# Isolation-Buffers.net
KiCad netlist of a schematic drawn in Altium Designer
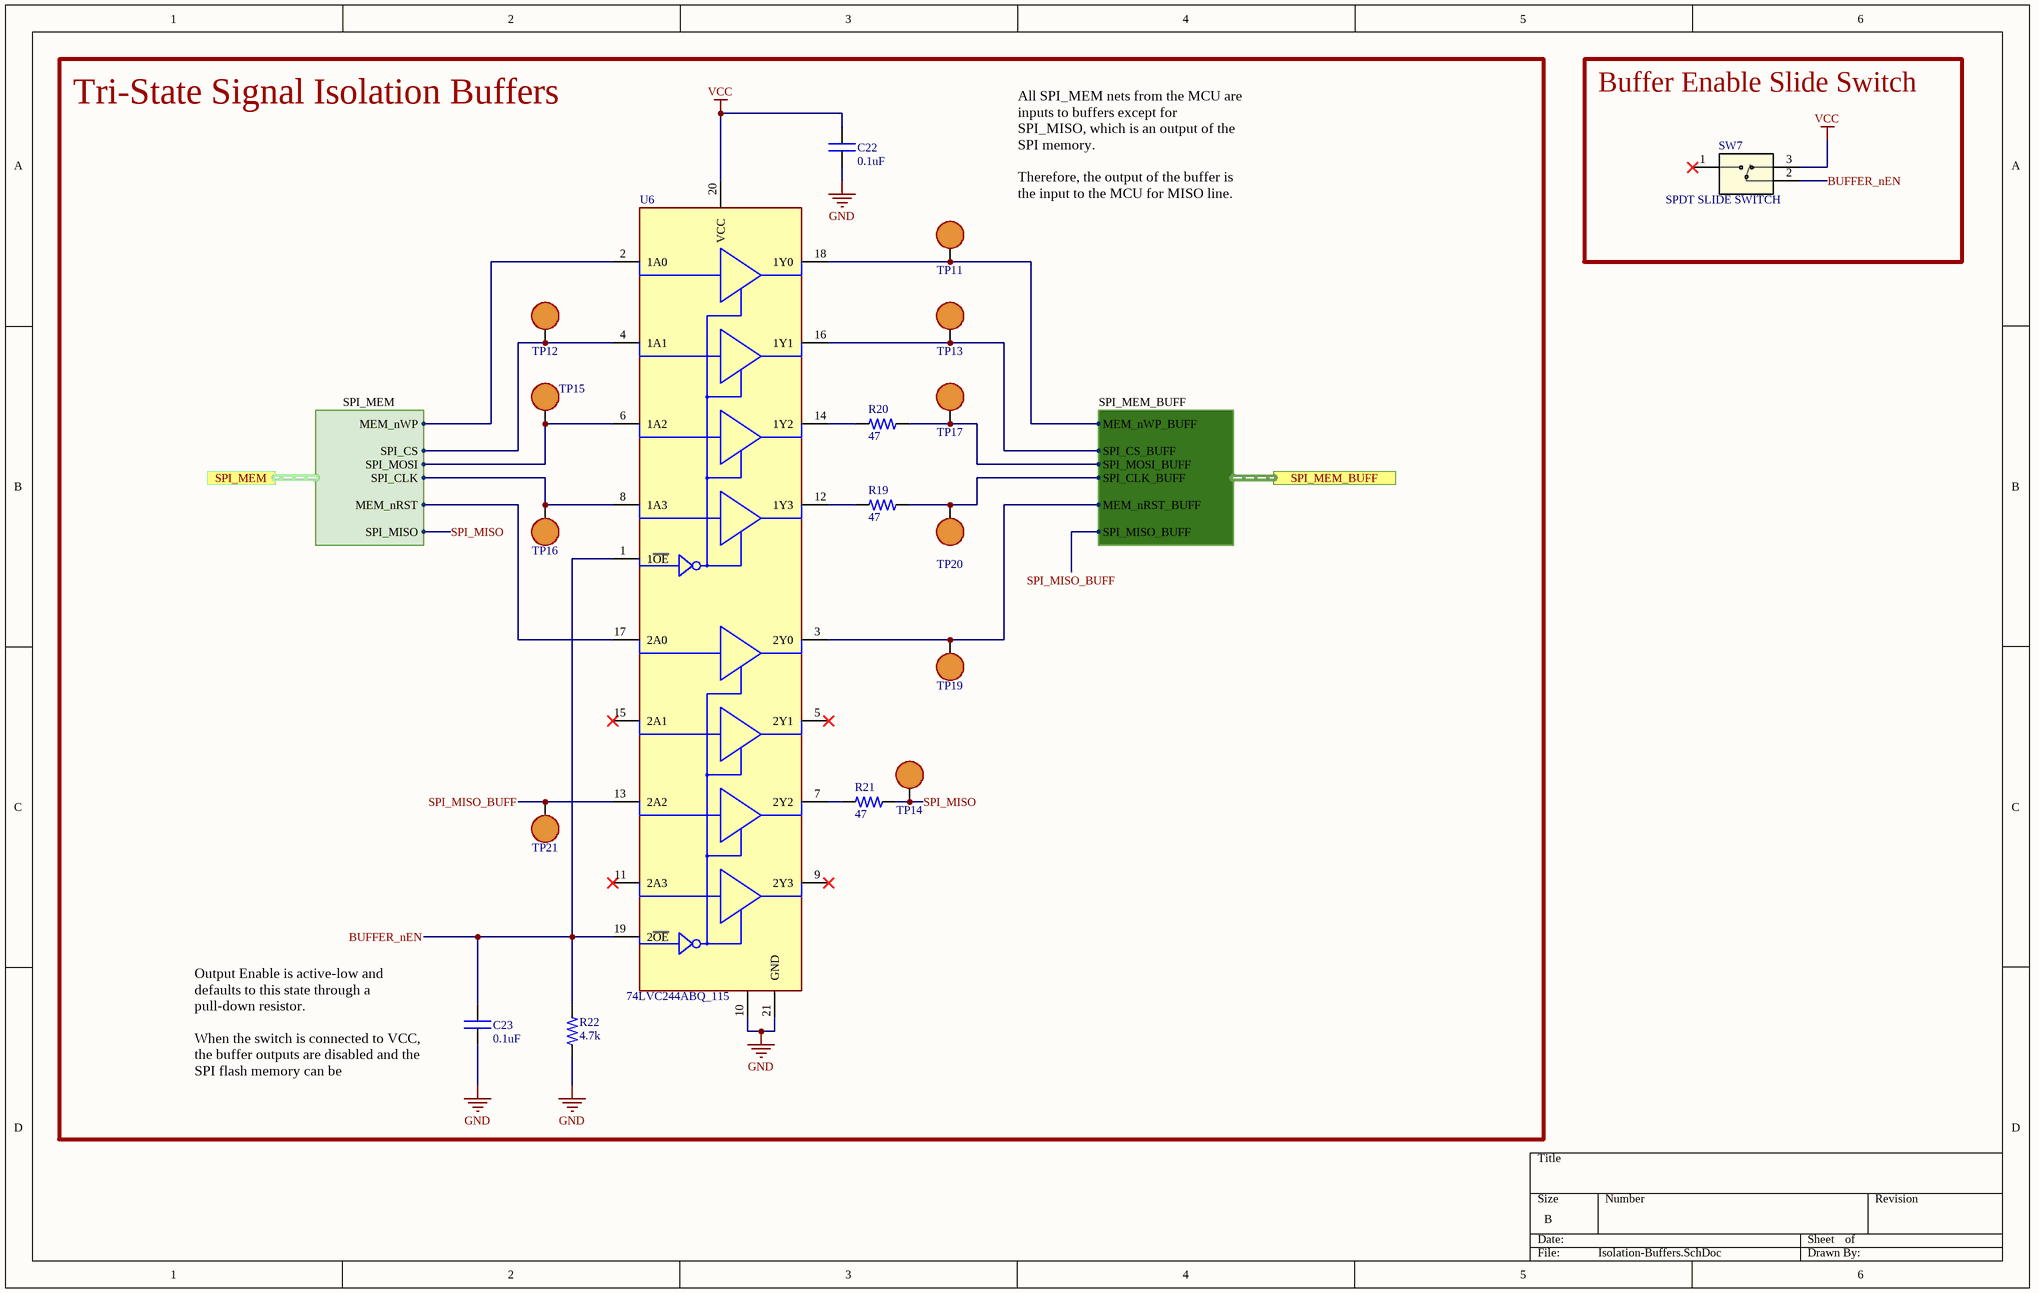
[diagram p0: Isolation-Buffers.SchDoc]

(export (version "E")
  (design (tool "Eeschema 10.0.6"))
  (components
    (comp (ref "C22")
      (value "0.1uF")
      (footprint "Beethoven-clock:0402C")
      (description "Capacitor")
      (fields (field (name "MFR") "Murata Electronics") (field (name "Comment") "CAP"))
      (libsource (lib "Beethoven-clock") (part "CAP"))
    )
    (comp (ref "C23")
      (value "0.1uF")
      (footprint "Beethoven-clock:0402C")
      (description "Capacitor")
      (fields (field (name "MFR") "Murata Electronics") (field (name "Comment") "CAP"))
      (libsource (lib "Beethoven-clock") (part "CAP"))
    )
    (comp (ref "R19")
      (value "47")
      (footprint "Beethoven-clock:0402R")
      (description "Resistor")
      (fields (field (name "MFR") "YAGEO") (field (name "Comment") "RES"))
      (libsource (lib "Beethoven-clock") (part "RES"))
    )
    (comp (ref "R20")
      (value "47")
      (footprint "Beethoven-clock:0402R")
      (description "Resistor")
      (fields (field (name "MFR") "YAGEO") (field (name "Comment") "RES"))
      (libsource (lib "Beethoven-clock") (part "RES"))
    )
    (comp (ref "R21")
      (value "47")
      (footprint "Beethoven-clock:0402R")
      (description "Resistor")
      (fields (field (name "MFR") "YAGEO") (field (name "Comment") "RES"))
      (libsource (lib "Beethoven-clock") (part "RES"))
    )
    (comp (ref "R22")
      (value "4.7k")
      (footprint "Beethoven-clock:0402R")
      (description "Resistor")
      (fields (field (name "MFR") "YAGEO") (field (name "Comment") "RES"))
      (libsource (lib "Beethoven-clock") (part "RES"))
    )
    (comp (ref "SW7")
      (value "SPDT SLIDE SWITCH")
      (footprint "Beethoven-clock:JS102011SCQN")
      (fields (field (name "MFR") "C&K"))
      (libsource (lib "Beethoven-clock") (part "SPDT SLIDE SWITCH"))
    )
    (comp (ref "TP11")
      (value "RCWCTE")
      (footprint "Beethoven-clock:RCWCTE")
      (description "Test Point, Surface Mount")
      (fields (field (name "MFR") "KOA Speer Electronics, Inc."))
      (libsource (lib "Beethoven-clock") (part "TEST POINT"))
    )
    (comp (ref "TP12")
      (value "RCWCTE")
      (footprint "Beethoven-clock:RCWCTE")
      (description "Test Point, Surface Mount")
      (fields (field (name "MFR") "KOA Speer Electronics, Inc."))
      (libsource (lib "Beethoven-clock") (part "TEST POINT"))
    )
    (comp (ref "TP13")
      (value "RCWCTE")
      (footprint "Beethoven-clock:RCWCTE")
      (description "Test Point, Surface Mount")
      (fields (field (name "MFR") "KOA Speer Electronics, Inc."))
      (libsource (lib "Beethoven-clock") (part "TEST POINT"))
    )
    (comp (ref "TP14")
      (value "RCWCTE")
      (footprint "Beethoven-clock:RCWCTE")
      (description "Test Point, Surface Mount")
      (fields (field (name "MFR") "KOA Speer Electronics, Inc."))
      (libsource (lib "Beethoven-clock") (part "TEST POINT"))
    )
    (comp (ref "TP15")
      (value "RCWCTE")
      (footprint "Beethoven-clock:RCWCTE")
      (description "Test Point, Surface Mount")
      (fields (field (name "MFR") "KOA Speer Electronics, Inc."))
      (libsource (lib "Beethoven-clock") (part "TEST POINT"))
    )
    (comp (ref "TP16")
      (value "RCWCTE")
      (footprint "Beethoven-clock:RCWCTE")
      (description "Test Point, Surface Mount")
      (fields (field (name "MFR") "KOA Speer Electronics, Inc."))
      (libsource (lib "Beethoven-clock") (part "TEST POINT"))
    )
    (comp (ref "TP17")
      (value "RCWCTE")
      (footprint "Beethoven-clock:RCWCTE")
      (description "Test Point, Surface Mount")
      (fields (field (name "MFR") "KOA Speer Electronics, Inc."))
      (libsource (lib "Beethoven-clock") (part "TEST POINT"))
    )
    (comp (ref "TP19")
      (value "RCWCTE")
      (footprint "Beethoven-clock:RCWCTE")
      (description "Test Point, Surface Mount")
      (fields (field (name "MFR") "KOA Speer Electronics, Inc."))
      (libsource (lib "Beethoven-clock") (part "TEST POINT"))
    )
    (comp (ref "TP20")
      (value "RCWCTE")
      (footprint "Beethoven-clock:RCWCTE")
      (description "Test Point, Surface Mount")
      (fields (field (name "MFR") "KOA Speer Electronics, Inc."))
      (libsource (lib "Beethoven-clock") (part "TEST POINT"))
    )
    (comp (ref "TP21")
      (value "RCWCTE")
      (footprint "Beethoven-clock:RCWCTE")
      (description "Test Point, Surface Mount")
      (fields (field (name "MFR") "KOA Speer Electronics, Inc."))
      (libsource (lib "Beethoven-clock") (part "TEST POINT"))
    )
    (comp (ref "U6")
      (value "74LVC244ABQ_115")
      (footprint "Beethoven-clock:20-VFQN-EP")
      (description "NXP 74LVC244ABQ,115 Octal Buffer & Line Driver, 3-State, 1.2  3.6 V, 20-Pin DHVQFN")
      (fields (field (name "MFR") "Nexperia"))
      (libsource (lib "Beethoven-clock") (part "TRI-STATE BUFFERS 8 CIRC"))
    )
  )
  (nets
    (net (code "3") (name "/BUFFER_nEN") (class "Default")
      (node (ref "C23") (pin "2") (pinfunction "2_2") (pintype "passive"))
      (node (ref "R22") (pin "2") (pinfunction "2_2") (pintype "passive"))
      (node (ref "SW7") (pin "2") (pinfunction "2_2") (pintype "passive"))
      (node (ref "U6") (pin "1") (pinfunction "1~{OE}_1") (pintype "passive"))
      (node (ref "U6") (pin "19") (pinfunction "2~{OE}_19") (pintype "passive"))
    )
    (net (code "4") (name "/MEM_nRST") (class "Default")
      (node (ref "U6") (pin "17") (pinfunction "2A0_17") (pintype "passive"))
    )
    (net (code "5") (name "/MEM_nRST_BUFF") (class "Default")
      (node (ref "TP19") (pin "1") (pinfunction "0_1") (pintype "passive"))
      (node (ref "U6") (pin "3") (pinfunction "2Y0_3") (pintype "passive"))
    )
    (net (code "6") (name "/MEM_nWP") (class "Default")
      (node (ref "U6") (pin "2") (pinfunction "1A0_2") (pintype "passive"))
    )
    (net (code "7") (name "/MEM_nWP_BUFF") (class "Default")
      (node (ref "TP11") (pin "1") (pinfunction "0_1") (pintype "passive"))
      (node (ref "U6") (pin "18") (pinfunction "1Y0_18") (pintype "passive"))
    )
    (net (code "8") (name "/SPI_CLK") (class "Default")
      (node (ref "TP16") (pin "1") (pinfunction "0_1") (pintype "passive"))
      (node (ref "U6") (pin "8") (pinfunction "1A3_8") (pintype "passive"))
    )
    (net (code "9") (name "/SPI_CLK_BUFF") (class "Default")
      (node (ref "R19") (pin "1") (pinfunction "1_1") (pintype "passive"))
      (node (ref "TP20") (pin "1") (pinfunction "0_1") (pintype "passive"))
    )
    (net (code "10") (name "/SPI_CS") (class "Default")
      (node (ref "TP12") (pin "1") (pinfunction "0_1") (pintype "passive"))
      (node (ref "U6") (pin "4") (pinfunction "1A1_4") (pintype "passive"))
    )
    (net (code "11") (name "/SPI_CS_BUFF") (class "Default")
      (node (ref "TP13") (pin "1") (pinfunction "0_1") (pintype "passive"))
      (node (ref "U6") (pin "16") (pinfunction "1Y1_16") (pintype "passive"))
    )
    (net (code "12") (name "/SPI_MISO") (class "Default")
      (node (ref "R21") (pin "1") (pinfunction "1_1") (pintype "passive"))
      (node (ref "TP14") (pin "1") (pinfunction "0_1") (pintype "passive"))
    )
    (net (code "13") (name "/SPI_MISO_BUFF") (class "Default")
      (node (ref "TP21") (pin "1") (pinfunction "0_1") (pintype "passive"))
      (node (ref "U6") (pin "13") (pinfunction "2A2_13") (pintype "passive"))
    )
    (net (code "14") (name "/SPI_MOSI") (class "Default")
      (node (ref "TP15") (pin "1") (pinfunction "0_1") (pintype "passive"))
      (node (ref "U6") (pin "6") (pinfunction "1A2_6") (pintype "passive"))
    )
    (net (code "15") (name "/SPI_MOSI_BUFF") (class "Default")
      (node (ref "R20") (pin "1") (pinfunction "1_1") (pintype "passive"))
      (node (ref "TP17") (pin "1") (pinfunction "0_1") (pintype "passive"))
    )
    (net (code "18") (name "GND") (class "Default")
      (node (ref "C22") (pin "2") (pinfunction "2_2") (pintype "passive"))
      (node (ref "C23") (pin "1") (pinfunction "1_1") (pintype "passive"))
      (node (ref "R22") (pin "1") (pinfunction "1_1") (pintype "passive"))
      (node (ref "U6") (pin "10") (pinfunction "GND_10") (pintype "passive"))
      (node (ref "U6") (pin "21") (pinfunction "GND_21") (pintype "passive"))
    )
    (net (code "19") (name "Net-(U6-1Y2)") (class "Default")
      (node (ref "R20") (pin "2") (pinfunction "2_2") (pintype "passive"))
      (node (ref "U6") (pin "14") (pinfunction "1Y2_14") (pintype "passive"))
    )
    (net (code "20") (name "Net-(U6-1Y3)") (class "Default")
      (node (ref "R19") (pin "2") (pinfunction "2_2") (pintype "passive"))
      (node (ref "U6") (pin "12") (pinfunction "1Y3_12") (pintype "passive"))
    )
    (net (code "21") (name "Net-(U6-2Y2)") (class "Default")
      (node (ref "R21") (pin "2") (pinfunction "2_2") (pintype "passive"))
      (node (ref "U6") (pin "7") (pinfunction "2Y2_7") (pintype "passive"))
    )
    (net (code "22") (name "VCC") (class "Default")
      (node (ref "C22") (pin "1") (pinfunction "1_1") (pintype "passive"))
      (node (ref "SW7") (pin "3") (pinfunction "3_3") (pintype "passive"))
      (node (ref "U6") (pin "20") (pinfunction "VCC_20") (pintype "passive"))
    )
    (net (code "23") (name "unconnected-(SW7-Pad1)") (class "Default")
      (node (ref "SW7") (pin "1") (pinfunction "1_1") (pintype "passive+no_connect"))
    )
    (net (code "24") (name "unconnected-(U6-2A1-Pad15)") (class "Default")
      (node (ref "U6") (pin "15") (pinfunction "2A1_15") (pintype "passive+no_connect"))
    )
    (net (code "25") (name "unconnected-(U6-2A3-Pad11)") (class "Default")
      (node (ref "U6") (pin "11") (pinfunction "2A3_11") (pintype "passive+no_connect"))
    )
    (net (code "26") (name "unconnected-(U6-2Y1-Pad5)") (class "Default")
      (node (ref "U6") (pin "5") (pinfunction "2Y1_5") (pintype "passive+no_connect"))
    )
    (net (code "27") (name "unconnected-(U6-2Y3-Pad9)") (class "Default")
      (node (ref "U6") (pin "9") (pinfunction "2Y3_9") (pintype "passive+no_connect"))
    )
  )
)
